# 2_DDR4_16bits.net
KiCad netlist of a schematic drawn in Altium Designer
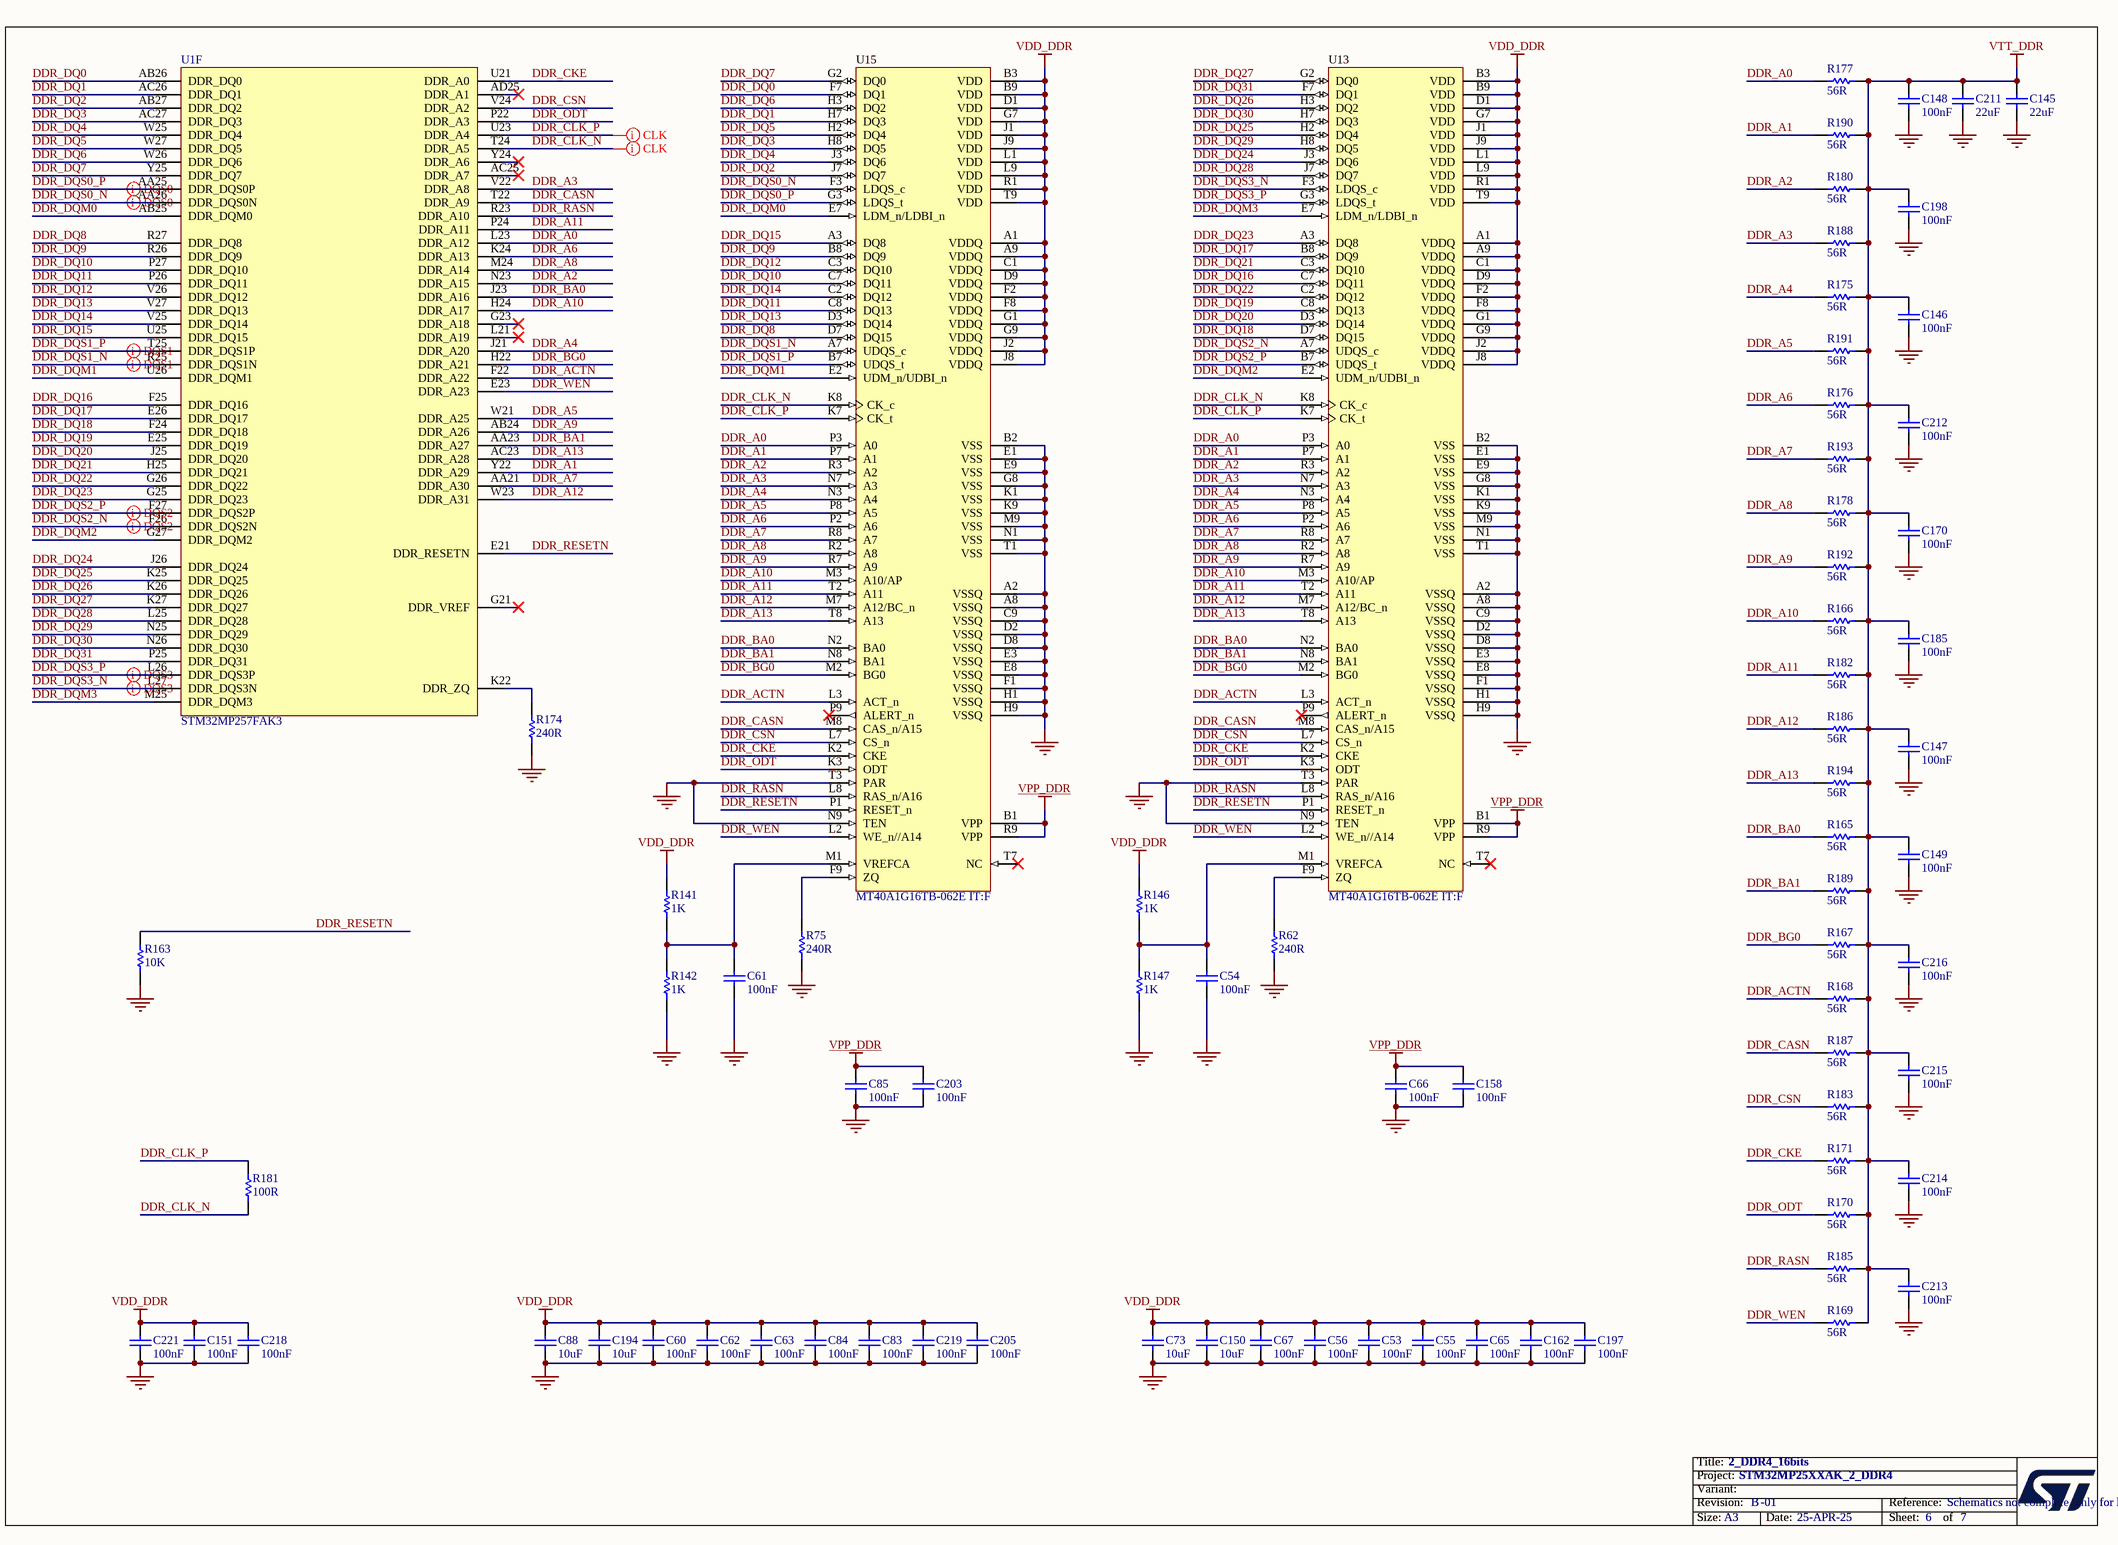
[diagram p0: 2_DDR4_16bits.SchDoc]

(export (version "E")
  (design (tool "Eeschema 10.0.6"))
  (components
    (comp (ref "C53")
      (value "100nF")
      (footprint "C0402")
      (description "Capacitor, MLCC, 100nF, 16V, X7R, +/-10%, 0402, T=0.5mm")
      (fields (field (name "INTERNAL_PART_NUMBER") "MCD-00006") (field (name "MANUFACTURER") "YAGEO"))
      (libsource (lib "MCD_PARTS_database") (part "Capacitor"))
    )
    (comp (ref "C54")
      (value "100nF")
      (footprint "C0402")
      (description "Capacitor, MLCC, 100nF, 16V, X7R, +/-10%, 0402, T=0.5mm")
      (fields (field (name "INTERNAL_PART_NUMBER") "MCD-00006") (field (name "MANUFACTURER") "YAGEO"))
      (libsource (lib "MCD_PARTS_database") (part "Capacitor"))
    )
    (comp (ref "C55")
      (value "100nF")
      (footprint "C0402")
      (description "Capacitor, MLCC, 100nF, 16V, X7R, +/-10%, 0402, T=0.5mm")
      (fields (field (name "INTERNAL_PART_NUMBER") "MCD-00006") (field (name "MANUFACTURER") "YAGEO"))
      (libsource (lib "MCD_PARTS_database") (part "Capacitor"))
    )
    (comp (ref "C56")
      (value "100nF")
      (footprint "C0402")
      (description "Capacitor, MLCC, 100nF, 16V, X7R, +/-10%, 0402, T=0.5mm")
      (fields (field (name "INTERNAL_PART_NUMBER") "MCD-00006") (field (name "MANUFACTURER") "YAGEO"))
      (libsource (lib "MCD_PARTS_database") (part "Capacitor"))
    )
    (comp (ref "C60")
      (value "100nF")
      (footprint "C0402")
      (description "Capacitor, MLCC, 100nF, 16V, X7R, +/-10%, 0402, T=0.5mm")
      (fields (field (name "INTERNAL_PART_NUMBER") "MCD-00006") (field (name "MANUFACTURER") "YAGEO"))
      (libsource (lib "MCD_PARTS_database") (part "Capacitor"))
    )
    (comp (ref "C61")
      (value "100nF")
      (footprint "C0402")
      (description "Capacitor, MLCC, 100nF, 16V, X7R, +/-10%, 0402, T=0.5mm")
      (fields (field (name "INTERNAL_PART_NUMBER") "MCD-00006") (field (name "MANUFACTURER") "YAGEO"))
      (libsource (lib "MCD_PARTS_database") (part "Capacitor"))
    )
    (comp (ref "C62")
      (value "100nF")
      (footprint "C0402")
      (description "Capacitor, MLCC, 100nF, 16V, X7R, +/-10%, 0402, T=0.5mm")
      (fields (field (name "INTERNAL_PART_NUMBER") "MCD-00006") (field (name "MANUFACTURER") "YAGEO"))
      (libsource (lib "MCD_PARTS_database") (part "Capacitor"))
    )
    (comp (ref "C63")
      (value "100nF")
      (footprint "C0402")
      (description "Capacitor, MLCC, 100nF, 16V, X7R, +/-10%, 0402, T=0.5mm")
      (fields (field (name "INTERNAL_PART_NUMBER") "MCD-00006") (field (name "MANUFACTURER") "YAGEO"))
      (libsource (lib "MCD_PARTS_database") (part "Capacitor"))
    )
    (comp (ref "C65")
      (value "100nF")
      (footprint "C0402")
      (description "Capacitor, MLCC, 100nF, 16V, X7R, +/-10%, 0402, T=0.5mm")
      (fields (field (name "INTERNAL_PART_NUMBER") "MCD-00006") (field (name "MANUFACTURER") "YAGEO"))
      (libsource (lib "MCD_PARTS_database") (part "Capacitor"))
    )
    (comp (ref "C66")
      (value "100nF")
      (footprint "C0402")
      (description "Capacitor, MLCC, 100nF, 16V, X7R, +/-10%, 0402, T=0.5mm")
      (fields (field (name "INTERNAL_PART_NUMBER") "MCD-00006") (field (name "MANUFACTURER") "YAGEO"))
      (libsource (lib "MCD_PARTS_database") (part "Capacitor"))
    )
    (comp (ref "C67")
      (value "100nF")
      (footprint "C0402")
      (description "Capacitor, MLCC, 100nF, 16V, X7R, +/-10%, 0402, T=0.5mm")
      (fields (field (name "INTERNAL_PART_NUMBER") "MCD-00006") (field (name "MANUFACTURER") "YAGEO"))
      (libsource (lib "MCD_PARTS_database") (part "Capacitor"))
    )
    (comp (ref "C73")
      (value "10uF")
      (footprint "C0603")
      (description "Capacitor, MLCC, 10uF, 6V3, X5R, +/-20%, 0603, T=0,8mm")
      (fields (field (name "INTERNAL_PART_NUMBER") "MCD-01341") (field (name "MANUFACTURER") "MURATA"))
      (libsource (lib "MCD_PARTS_database") (part "Capacitor"))
    )
    (comp (ref "C83")
      (value "100nF")
      (footprint "C0402")
      (description "Capacitor, MLCC, 100nF, 16V, X7R, +/-10%, 0402, T=0.5mm")
      (fields (field (name "INTERNAL_PART_NUMBER") "MCD-00006") (field (name "MANUFACTURER") "YAGEO"))
      (libsource (lib "MCD_PARTS_database") (part "Capacitor"))
    )
    (comp (ref "C84")
      (value "100nF")
      (footprint "C0402")
      (description "Capacitor, MLCC, 100nF, 16V, X7R, +/-10%, 0402, T=0.5mm")
      (fields (field (name "INTERNAL_PART_NUMBER") "MCD-00006") (field (name "MANUFACTURER") "YAGEO"))
      (libsource (lib "MCD_PARTS_database") (part "Capacitor"))
    )
    (comp (ref "C85")
      (value "100nF")
      (footprint "C0402")
      (description "Capacitor, MLCC, 100nF, 16V, X7R, +/-10%, 0402, T=0.5mm")
      (fields (field (name "INTERNAL_PART_NUMBER") "MCD-00006") (field (name "MANUFACTURER") "YAGEO"))
      (libsource (lib "MCD_PARTS_database") (part "Capacitor"))
    )
    (comp (ref "C88")
      (value "10uF")
      (footprint "C0603")
      (description "Capacitor, MLCC, 10uF, 6V3, X5R, +/-20%, 0603, T=0,8mm")
      (fields (field (name "INTERNAL_PART_NUMBER") "MCD-01341") (field (name "MANUFACTURER") "MURATA"))
      (libsource (lib "MCD_PARTS_database") (part "Capacitor"))
    )
    (comp (ref "C145")
      (value "22uF")
      (footprint "C0603")
      (description "Capacitor, MLCC, 22uF, 6V3, X5R, +/-20%, 0603, T=0,8mm")
      (fields (field (name "INTERNAL_PART_NUMBER") "MCD-00100") (field (name "MANUFACTURER") "MURATA"))
      (libsource (lib "MCD_PARTS_database") (part "Capacitor"))
    )
    (comp (ref "C146")
      (value "100nF")
      (footprint "C0402")
      (description "Capacitor, MLCC, 100nF, 16V, X7R, +/-10%, 0402, T=0.5mm")
      (fields (field (name "INTERNAL_PART_NUMBER") "MCD-00006") (field (name "MANUFACTURER") "YAGEO"))
      (libsource (lib "MCD_PARTS_database") (part "Capacitor"))
    )
    (comp (ref "C147")
      (value "100nF")
      (footprint "C0402")
      (description "Capacitor, MLCC, 100nF, 16V, X7R, +/-10%, 0402, T=0.5mm")
      (fields (field (name "INTERNAL_PART_NUMBER") "MCD-00006") (field (name "MANUFACTURER") "YAGEO"))
      (libsource (lib "MCD_PARTS_database") (part "Capacitor"))
    )
    (comp (ref "C148")
      (value "100nF")
      (footprint "C0402")
      (description "Capacitor, MLCC, 100nF, 16V, X7R, +/-10%, 0402, T=0.5mm")
      (fields (field (name "INTERNAL_PART_NUMBER") "MCD-00006") (field (name "MANUFACTURER") "YAGEO"))
      (libsource (lib "MCD_PARTS_database") (part "Capacitor"))
    )
    (comp (ref "C149")
      (value "100nF")
      (footprint "C0402")
      (description "Capacitor, MLCC, 100nF, 16V, X7R, +/-10%, 0402, T=0.5mm")
      (fields (field (name "INTERNAL_PART_NUMBER") "MCD-00006") (field (name "MANUFACTURER") "YAGEO"))
      (libsource (lib "MCD_PARTS_database") (part "Capacitor"))
    )
    (comp (ref "C150")
      (value "10uF")
      (footprint "C0603")
      (description "Capacitor, MLCC, 10uF, 6V3, X5R, +/-20%, 0603, T=0,8mm")
      (fields (field (name "INTERNAL_PART_NUMBER") "MCD-01341") (field (name "MANUFACTURER") "MURATA"))
      (libsource (lib "MCD_PARTS_database") (part "Capacitor"))
    )
    (comp (ref "C151")
      (value "100nF")
      (footprint "C0402")
      (description "Capacitor, MLCC, 100nF, 16V, X7R, +/-10%, 0402, T=0.5mm")
      (fields (field (name "INTERNAL_PART_NUMBER") "MCD-00006") (field (name "MANUFACTURER") "YAGEO"))
      (libsource (lib "MCD_PARTS_database") (part "Capacitor"))
    )
    (comp (ref "C158")
      (value "100nF")
      (footprint "C0402")
      (description "Capacitor, MLCC, 100nF, 16V, X7R, +/-10%, 0402, T=0.5mm")
      (fields (field (name "INTERNAL_PART_NUMBER") "MCD-00006") (field (name "MANUFACTURER") "YAGEO"))
      (libsource (lib "MCD_PARTS_database") (part "Capacitor"))
    )
    (comp (ref "C162")
      (value "100nF")
      (footprint "C0402")
      (description "Capacitor, MLCC, 100nF, 16V, X7R, +/-10%, 0402, T=0.5mm")
      (fields (field (name "INTERNAL_PART_NUMBER") "MCD-00006") (field (name "MANUFACTURER") "YAGEO"))
      (libsource (lib "MCD_PARTS_database") (part "Capacitor"))
    )
    (comp (ref "C170")
      (value "100nF")
      (footprint "C0402")
      (description "Capacitor, MLCC, 100nF, 16V, X7R, +/-10%, 0402, T=0.5mm")
      (fields (field (name "INTERNAL_PART_NUMBER") "MCD-00006") (field (name "MANUFACTURER") "YAGEO"))
      (libsource (lib "MCD_PARTS_database") (part "Capacitor"))
    )
    (comp (ref "C185")
      (value "100nF")
      (footprint "C0402")
      (description "Capacitor, MLCC, 100nF, 16V, X7R, +/-10%, 0402, T=0.5mm")
      (fields (field (name "INTERNAL_PART_NUMBER") "MCD-00006") (field (name "MANUFACTURER") "YAGEO"))
      (libsource (lib "MCD_PARTS_database") (part "Capacitor"))
    )
    (comp (ref "C194")
      (value "10uF")
      (footprint "C0603")
      (description "Capacitor, MLCC, 10uF, 6V3, X5R, +/-20%, 0603, T=0,8mm")
      (fields (field (name "INTERNAL_PART_NUMBER") "MCD-01341") (field (name "MANUFACTURER") "MURATA"))
      (libsource (lib "MCD_PARTS_database") (part "Capacitor"))
    )
    (comp (ref "C197")
      (value "100nF")
      (footprint "C0402")
      (description "Capacitor, MLCC, 100nF, 16V, X7R, +/-10%, 0402, T=0.5mm")
      (fields (field (name "INTERNAL_PART_NUMBER") "MCD-00006") (field (name "MANUFACTURER") "YAGEO"))
      (libsource (lib "MCD_PARTS_database") (part "Capacitor"))
    )
    (comp (ref "C198")
      (value "100nF")
      (footprint "C0402")
      (description "Capacitor, MLCC, 100nF, 16V, X7R, +/-10%, 0402, T=0.5mm")
      (fields (field (name "INTERNAL_PART_NUMBER") "MCD-00006") (field (name "MANUFACTURER") "YAGEO"))
      (libsource (lib "MCD_PARTS_database") (part "Capacitor"))
    )
    (comp (ref "C203")
      (value "100nF")
      (footprint "C0402")
      (description "Capacitor, MLCC, 100nF, 16V, X7R, +/-10%, 0402, T=0.5mm")
      (fields (field (name "INTERNAL_PART_NUMBER") "MCD-00006") (field (name "MANUFACTURER") "YAGEO"))
      (libsource (lib "MCD_PARTS_database") (part "Capacitor"))
    )
    (comp (ref "C205")
      (value "100nF")
      (footprint "C0402")
      (description "Capacitor, MLCC, 100nF, 16V, X7R, +/-10%, 0402, T=0.5mm")
      (fields (field (name "INTERNAL_PART_NUMBER") "MCD-00006") (field (name "MANUFACTURER") "YAGEO"))
      (libsource (lib "MCD_PARTS_database") (part "Capacitor"))
    )
    (comp (ref "C211")
      (value "22uF")
      (footprint "C0603")
      (description "Capacitor, MLCC, 22uF, 6V3, X5R, +/-20%, 0603, T=0,8mm")
      (fields (field (name "INTERNAL_PART_NUMBER") "MCD-00100") (field (name "MANUFACTURER") "MURATA"))
      (libsource (lib "MCD_PARTS_database") (part "Capacitor"))
    )
    (comp (ref "C212")
      (value "100nF")
      (footprint "C0402")
      (description "Capacitor, MLCC, 100nF, 16V, X7R, +/-10%, 0402, T=0.5mm")
      (fields (field (name "INTERNAL_PART_NUMBER") "MCD-00006") (field (name "MANUFACTURER") "YAGEO"))
      (libsource (lib "MCD_PARTS_database") (part "Capacitor"))
    )
    (comp (ref "C213")
      (value "100nF")
      (footprint "C0402")
      (description "Capacitor, MLCC, 100nF, 16V, X7R, +/-10%, 0402, T=0.5mm")
      (fields (field (name "INTERNAL_PART_NUMBER") "MCD-00006") (field (name "MANUFACTURER") "YAGEO"))
      (libsource (lib "MCD_PARTS_database") (part "Capacitor"))
    )
    (comp (ref "C214")
      (value "100nF")
      (footprint "C0402")
      (description "Capacitor, MLCC, 100nF, 16V, X7R, +/-10%, 0402, T=0.5mm")
      (fields (field (name "INTERNAL_PART_NUMBER") "MCD-00006") (field (name "MANUFACTURER") "YAGEO"))
      (libsource (lib "MCD_PARTS_database") (part "Capacitor"))
    )
    (comp (ref "C215")
      (value "100nF")
      (footprint "C0402")
      (description "Capacitor, MLCC, 100nF, 16V, X7R, +/-10%, 0402, T=0.5mm")
      (fields (field (name "INTERNAL_PART_NUMBER") "MCD-00006") (field (name "MANUFACTURER") "YAGEO"))
      (libsource (lib "MCD_PARTS_database") (part "Capacitor"))
    )
    (comp (ref "C216")
      (value "100nF")
      (footprint "C0402")
      (description "Capacitor, MLCC, 100nF, 16V, X7R, +/-10%, 0402, T=0.5mm")
      (fields (field (name "INTERNAL_PART_NUMBER") "MCD-00006") (field (name "MANUFACTURER") "YAGEO"))
      (libsource (lib "MCD_PARTS_database") (part "Capacitor"))
    )
    (comp (ref "C218")
      (value "100nF")
      (footprint "C0402")
      (description "Capacitor, MLCC, 100nF, 16V, X7R, +/-10%, 0402, T=0.5mm")
      (fields (field (name "INTERNAL_PART_NUMBER") "MCD-00006") (field (name "MANUFACTURER") "YAGEO"))
      (libsource (lib "MCD_PARTS_database") (part "Capacitor"))
    )
    (comp (ref "C219")
      (value "100nF")
      (footprint "C0402")
      (description "Capacitor, MLCC, 100nF, 16V, X7R, +/-10%, 0402, T=0.5mm")
      (fields (field (name "INTERNAL_PART_NUMBER") "MCD-00006") (field (name "MANUFACTURER") "YAGEO"))
      (libsource (lib "MCD_PARTS_database") (part "Capacitor"))
    )
    (comp (ref "C221")
      (value "100nF")
      (footprint "C0402")
      (description "Capacitor, MLCC, 100nF, 16V, X7R, +/-10%, 0402, T=0.5mm")
      (fields (field (name "INTERNAL_PART_NUMBER") "MCD-00006") (field (name "MANUFACTURER") "YAGEO"))
      (libsource (lib "MCD_PARTS_database") (part "Capacitor"))
    )
    (comp (ref "R62")
      (value "240R")
      (footprint "R0201_H0P23")
      (description "Resistor,240R,0201,1%,1/20W")
      (fields (field (name "INTERNAL_PART_NUMBER") "MCD-02253") (field (name "MANUFACTURER") "YAGEO"))
      (libsource (lib "MCD_PARTS_database") (part "Resistor"))
    )
    (comp (ref "R75")
      (value "240R")
      (footprint "R0201_H0P23")
      (description "Resistor,240R,0201,1%,1/20W")
      (fields (field (name "INTERNAL_PART_NUMBER") "MCD-02253") (field (name "MANUFACTURER") "YAGEO"))
      (libsource (lib "MCD_PARTS_database") (part "Resistor"))
    )
    (comp (ref "R141")
      (value "1K")
      (footprint "R0402")
      (description "Resistor, 1K, 0402, +/-1%,1/16W")
      (fields (field (name "INTERNAL_PART_NUMBER") "MCD-00061") (field (name "MANUFACTURER") "YAGEO"))
      (libsource (lib "MCD_PARTS_database") (part "Resistor"))
    )
    (comp (ref "R142")
      (value "1K")
      (footprint "R0402")
      (description "Resistor, 1K, 0402, +/-1%,1/16W")
      (fields (field (name "INTERNAL_PART_NUMBER") "MCD-00061") (field (name "MANUFACTURER") "YAGEO"))
      (libsource (lib "MCD_PARTS_database") (part "Resistor"))
    )
    (comp (ref "R146")
      (value "1K")
      (footprint "R0402")
      (description "Resistor, 1K, 0402, +/-1%,1/16W")
      (fields (field (name "INTERNAL_PART_NUMBER") "MCD-00061") (field (name "MANUFACTURER") "YAGEO"))
      (libsource (lib "MCD_PARTS_database") (part "Resistor"))
    )
    (comp (ref "R147")
      (value "1K")
      (footprint "R0402")
      (description "Resistor, 1K, 0402, +/-1%,1/16W")
      (fields (field (name "INTERNAL_PART_NUMBER") "MCD-00061") (field (name "MANUFACTURER") "YAGEO"))
      (libsource (lib "MCD_PARTS_database") (part "Resistor"))
    )
    (comp (ref "R163")
      (value "10K")
      (footprint "R0402")
      (description "Resistor,10K,0402,1%,1/16W")
      (fields (field (name "INTERNAL_PART_NUMBER") "MCD-00053") (field (name "BMS_PART_NUMBER") "9131590"))
      (libsource (lib "MCD_PARTS_database") (part "Resistor"))
    )
    (comp (ref "R165")
      (value "56R")
      (footprint "R0402")
      (description "Resistor, 56R, 0402, +/-1%, 1/16W")
      (fields (field (name "INTERNAL_PART_NUMBER") "MCD-00054") (field (name "MANUFACTURER") "YAGEO"))
      (libsource (lib "MCD_PARTS_database") (part "Resistor"))
    )
    (comp (ref "R166")
      (value "56R")
      (footprint "R0402")
      (description "Resistor, 56R, 0402, +/-1%, 1/16W")
      (fields (field (name "INTERNAL_PART_NUMBER") "MCD-00054") (field (name "MANUFACTURER") "YAGEO"))
      (libsource (lib "MCD_PARTS_database") (part "Resistor"))
    )
    (comp (ref "R167")
      (value "56R")
      (footprint "R0402")
      (description "Resistor, 56R, 0402, +/-1%, 1/16W")
      (fields (field (name "INTERNAL_PART_NUMBER") "MCD-00054") (field (name "MANUFACTURER") "YAGEO"))
      (libsource (lib "MCD_PARTS_database") (part "Resistor"))
    )
    (comp (ref "R168")
      (value "56R")
      (footprint "R0402")
      (description "Resistor, 56R, 0402, +/-1%, 1/16W")
      (fields (field (name "INTERNAL_PART_NUMBER") "MCD-00054") (field (name "MANUFACTURER") "YAGEO"))
      (libsource (lib "MCD_PARTS_database") (part "Resistor"))
    )
    (comp (ref "R169")
      (value "56R")
      (footprint "R0402")
      (description "Resistor, 56R, 0402, +/-1%, 1/16W")
      (fields (field (name "INTERNAL_PART_NUMBER") "MCD-00054") (field (name "MANUFACTURER") "YAGEO"))
      (libsource (lib "MCD_PARTS_database") (part "Resistor"))
    )
    (comp (ref "R170")
      (value "56R")
      (footprint "R0402")
      (description "Resistor, 56R, 0402, +/-1%, 1/16W")
      (fields (field (name "INTERNAL_PART_NUMBER") "MCD-00054") (field (name "MANUFACTURER") "YAGEO"))
      (libsource (lib "MCD_PARTS_database") (part "Resistor"))
    )
    (comp (ref "R171")
      (value "56R")
      (footprint "R0402")
      (description "Resistor, 56R, 0402, +/-1%, 1/16W")
      (fields (field (name "INTERNAL_PART_NUMBER") "MCD-00054") (field (name "MANUFACTURER") "YAGEO"))
      (libsource (lib "MCD_PARTS_database") (part "Resistor"))
    )
    (comp (ref "R174")
      (value "240R")
      (footprint "R0201_H0P23")
      (description "Resistor,240R,0201,1%,1/20W")
      (fields (field (name "INTERNAL_PART_NUMBER") "MCD-02253") (field (name "MANUFACTURER") "YAGEO"))
      (libsource (lib "MCD_PARTS_database") (part "Resistor"))
    )
    (comp (ref "R175")
      (value "56R")
      (footprint "R0402")
      (description "Resistor, 56R, 0402, +/-1%, 1/16W")
      (fields (field (name "INTERNAL_PART_NUMBER") "MCD-00054") (field (name "MANUFACTURER") "YAGEO"))
      (libsource (lib "MCD_PARTS_database") (part "Resistor"))
    )
    (comp (ref "R176")
      (value "56R")
      (footprint "R0402")
      (description "Resistor, 56R, 0402, +/-1%, 1/16W")
      (fields (field (name "INTERNAL_PART_NUMBER") "MCD-00054") (field (name "MANUFACTURER") "YAGEO"))
      (libsource (lib "MCD_PARTS_database") (part "Resistor"))
    )
    (comp (ref "R177")
      (value "56R")
      (footprint "R0402")
      (description "Resistor, 56R, 0402, +/-1%, 1/16W")
      (fields (field (name "INTERNAL_PART_NUMBER") "MCD-00054") (field (name "MANUFACTURER") "YAGEO"))
      (libsource (lib "MCD_PARTS_database") (part "Resistor"))
    )
    (comp (ref "R178")
      (value "56R")
      (footprint "R0402")
      (description "Resistor, 56R, 0402, +/-1%, 1/16W")
      (fields (field (name "INTERNAL_PART_NUMBER") "MCD-00054") (field (name "MANUFACTURER") "YAGEO"))
      (libsource (lib "MCD_PARTS_database") (part "Resistor"))
    )
    (comp (ref "R180")
      (value "56R")
      (footprint "R0402")
      (description "Resistor, 56R, 0402, +/-1%, 1/16W")
      (fields (field (name "INTERNAL_PART_NUMBER") "MCD-00054") (field (name "MANUFACTURER") "YAGEO"))
      (libsource (lib "MCD_PARTS_database") (part "Resistor"))
    )
    (comp (ref "R181")
      (value "100R")
      (footprint "R0402")
      (description "Resistor,100R,0402,0,5%,1/16W,±100ppm/°C")
      (fields (field (name "INTERNAL_PART_NUMBER") "MCD-01819") (field (name "MANUFACTURER") "YAGEO"))
      (libsource (lib "MCD_PARTS_database") (part "Resistor"))
    )
    (comp (ref "R182")
      (value "56R")
      (footprint "R0402")
      (description "Resistor, 56R, 0402, +/-1%, 1/16W")
      (fields (field (name "INTERNAL_PART_NUMBER") "MCD-00054") (field (name "MANUFACTURER") "YAGEO"))
      (libsource (lib "MCD_PARTS_database") (part "Resistor"))
    )
    (comp (ref "R183")
      (value "56R")
      (footprint "R0402")
      (description "Resistor, 56R, 0402, +/-1%, 1/16W")
      (fields (field (name "INTERNAL_PART_NUMBER") "MCD-00054") (field (name "MANUFACTURER") "YAGEO"))
      (libsource (lib "MCD_PARTS_database") (part "Resistor"))
    )
    (comp (ref "R185")
      (value "56R")
      (footprint "R0402")
      (description "Resistor, 56R, 0402, +/-1%, 1/16W")
      (fields (field (name "INTERNAL_PART_NUMBER") "MCD-00054") (field (name "MANUFACTURER") "YAGEO"))
      (libsource (lib "MCD_PARTS_database") (part "Resistor"))
    )
    (comp (ref "R186")
      (value "56R")
      (footprint "R0402")
      (description "Resistor, 56R, 0402, +/-1%, 1/16W")
      (fields (field (name "INTERNAL_PART_NUMBER") "MCD-00054") (field (name "MANUFACTURER") "YAGEO"))
      (libsource (lib "MCD_PARTS_database") (part "Resistor"))
    )
    (comp (ref "R187")
      (value "56R")
      (footprint "R0402")
      (description "Resistor, 56R, 0402, +/-1%, 1/16W")
      (fields (field (name "INTERNAL_PART_NUMBER") "MCD-00054") (field (name "MANUFACTURER") "YAGEO"))
      (libsource (lib "MCD_PARTS_database") (part "Resistor"))
    )
    (comp (ref "R188")
      (value "56R")
      (footprint "R0402")
      (description "Resistor, 56R, 0402, +/-1%, 1/16W")
      (fields (field (name "INTERNAL_PART_NUMBER") "MCD-00054") (field (name "MANUFACTURER") "YAGEO"))
      (libsource (lib "MCD_PARTS_database") (part "Resistor"))
    )
    (comp (ref "R189")
      (value "56R")
      (footprint "R0402")
      (description "Resistor, 56R, 0402, +/-1%, 1/16W")
      (fields (field (name "INTERNAL_PART_NUMBER") "MCD-00054") (field (name "MANUFACTURER") "YAGEO"))
      (libsource (lib "MCD_PARTS_database") (part "Resistor"))
    )
    (comp (ref "R190")
      (value "56R")
      (footprint "R0402")
      (description "Resistor, 56R, 0402, +/-1%, 1/16W")
      (fields (field (name "INTERNAL_PART_NUMBER") "MCD-00054") (field (name "MANUFACTURER") "YAGEO"))
      (libsource (lib "MCD_PARTS_database") (part "Resistor"))
    )
    (comp (ref "R191")
      (value "56R")
      (footprint "R0402")
      (description "Resistor, 56R, 0402, +/-1%, 1/16W")
      (fields (field (name "INTERNAL_PART_NUMBER") "MCD-00054") (field (name "MANUFACTURER") "YAGEO"))
      (libsource (lib "MCD_PARTS_database") (part "Resistor"))
    )
    (comp (ref "R192")
      (value "56R")
      (footprint "R0402")
      (description "Resistor, 56R, 0402, +/-1%, 1/16W")
      (fields (field (name "INTERNAL_PART_NUMBER") "MCD-00054") (field (name "MANUFACTURER") "YAGEO"))
      (libsource (lib "MCD_PARTS_database") (part "Resistor"))
    )
    (comp (ref "R193")
      (value "56R")
      (footprint "R0402")
      (description "Resistor, 56R, 0402, +/-1%, 1/16W")
      (fields (field (name "INTERNAL_PART_NUMBER") "MCD-00054") (field (name "MANUFACTURER") "YAGEO"))
      (libsource (lib "MCD_PARTS_database") (part "Resistor"))
    )
    (comp (ref "R194")
      (value "56R")
      (footprint "R0402")
      (description "Resistor, 56R, 0402, +/-1%, 1/16W")
      (fields (field (name "INTERNAL_PART_NUMBER") "MCD-00054") (field (name "MANUFACTURER") "YAGEO"))
      (libsource (lib "MCD_PARTS_database") (part "Resistor"))
    )
    (comp (ref "U1")
      (value "STM32MP257FAK3")
      (footprint "ICC_TFBGA424_14X14_P050_H1P20_CODE-B0A2")
      (description "MPU , 2xCortex-A35@1.5GHz, Cortex-M33@400MHz, TFBGA 14x14, pitch 0.5, 648KB SRAM, With Crypto")
      (fields
        (field (name "INTERNAL_PART_NUMBER") "MCD-03375")
        (field (name "MANUFACTURER") "STMICROELECTRONICS")
      )
      (libsource (lib "MCD_PARTS_database") (part "STM32MP257FAK3"))
    )
    (comp (ref "U13")
      (value "MT40A1G16TB-062E IT:F")
      (footprint "ICC_FBGA96_TB_7P5X13_P080")
      (description "Memory, DDR4 SDRAM, 1V2, 16Gbit, FBGA96")
      (fields (field (name "INTERNAL_PART_NUMBER") "MCD-03523") (field (name "MANUFACTURER") "MICRON"))
      (libsource (lib "MCD_PARTS_database") (part "MT40A1G16TB-062E IT{colon}F"))
    )
    (comp (ref "U15")
      (value "MT40A1G16TB-062E IT:F")
      (footprint "ICC_FBGA96_TB_7P5X13_P080")
      (description "Memory, DDR4 SDRAM, 1V2, 16Gbit, FBGA96")
      (fields (field (name "INTERNAL_PART_NUMBER") "MCD-03523") (field (name "MANUFACTURER") "MICRON"))
      (libsource (lib "MCD_PARTS_database") (part "MT40A1G16TB-062E IT{colon}F"))
    )
  )
  (nets
    (net (code "1") (name "/DDR_A0") (class "Default")
      (node (ref "R177") (pin "1") (pinfunction "1_1") (pintype "passive"))
      (node (ref "U1") (pin "L23") (pinfunction "DDR_A12_L23") (pintype "passive"))
      (node (ref "U13") (pin "P3") (pinfunction "A0_P3") (pintype "input"))
      (node (ref "U15") (pin "P3") (pinfunction "A0_P3") (pintype "input"))
    )
    (net (code "2") (name "/DDR_A1") (class "Default")
      (node (ref "R190") (pin "1") (pinfunction "1_1") (pintype "passive"))
      (node (ref "U1") (pin "Y22") (pinfunction "DDR_A29_Y22") (pintype "passive"))
      (node (ref "U13") (pin "P7") (pinfunction "A1_P7") (pintype "input"))
      (node (ref "U15") (pin "P7") (pinfunction "A1_P7") (pintype "input"))
    )
    (net (code "3") (name "/DDR_A2") (class "Default")
      (node (ref "R180") (pin "1") (pinfunction "1_1") (pintype "passive"))
      (node (ref "U1") (pin "N23") (pinfunction "DDR_A15_N23") (pintype "passive"))
      (node (ref "U13") (pin "R3") (pinfunction "A2_R3") (pintype "input"))
      (node (ref "U15") (pin "R3") (pinfunction "A2_R3") (pintype "input"))
    )
    (net (code "4") (name "/DDR_A3") (class "Default")
      (node (ref "R188") (pin "1") (pinfunction "1_1") (pintype "passive"))
      (node (ref "U1") (pin "V22") (pinfunction "DDR_A8_V22") (pintype "passive"))
      (node (ref "U13") (pin "N7") (pinfunction "A3_N7") (pintype "input"))
      (node (ref "U15") (pin "N7") (pinfunction "A3_N7") (pintype "input"))
    )
    (net (code "5") (name "/DDR_A4") (class "Default")
      (node (ref "R175") (pin "1") (pinfunction "1_1") (pintype "passive"))
      (node (ref "U1") (pin "J21") (pinfunction "DDR_A20_J21") (pintype "passive"))
      (node (ref "U13") (pin "N3") (pinfunction "A4_N3") (pintype "input"))
      (node (ref "U15") (pin "N3") (pinfunction "A4_N3") (pintype "input"))
    )
    (net (code "6") (name "/DDR_A5") (class "Default")
      (node (ref "R191") (pin "1") (pinfunction "1_1") (pintype "passive"))
      (node (ref "U1") (pin "W21") (pinfunction "DDR_A25_W21") (pintype "passive"))
      (node (ref "U13") (pin "P8") (pinfunction "A5_P8") (pintype "input"))
      (node (ref "U15") (pin "P8") (pinfunction "A5_P8") (pintype "input"))
    )
    (net (code "7") (name "/DDR_A6") (class "Default")
      (node (ref "R176") (pin "1") (pinfunction "1_1") (pintype "passive"))
      (node (ref "U1") (pin "K24") (pinfunction "DDR_A13_K24") (pintype "passive"))
      (node (ref "U13") (pin "P2") (pinfunction "A6_P2") (pintype "input"))
      (node (ref "U15") (pin "P2") (pinfunction "A6_P2") (pintype "input"))
    )
    (net (code "8") (name "/DDR_A7") (class "Default")
      (node (ref "R193") (pin "1") (pinfunction "1_1") (pintype "passive"))
      (node (ref "U1") (pin "AA21") (pinfunction "DDR_A30_AA21") (pintype "passive"))
      (node (ref "U13") (pin "R8") (pinfunction "A7_R8") (pintype "input"))
      (node (ref "U15") (pin "R8") (pinfunction "A7_R8") (pintype "input"))
    )
    (net (code "9") (name "/DDR_A8") (class "Default")
      (node (ref "R178") (pin "1") (pinfunction "1_1") (pintype "passive"))
      (node (ref "U1") (pin "M24") (pinfunction "DDR_A14_M24") (pintype "passive"))
      (node (ref "U13") (pin "R2") (pinfunction "A8_R2") (pintype "input"))
      (node (ref "U15") (pin "R2") (pinfunction "A8_R2") (pintype "input"))
    )
    (net (code "10") (name "/DDR_A9") (class "Default")
      (node (ref "R192") (pin "1") (pinfunction "1_1") (pintype "passive"))
      (node (ref "U1") (pin "AB24") (pinfunction "DDR_A26_AB24") (pintype "passive"))
      (node (ref "U13") (pin "R7") (pinfunction "A9_R7") (pintype "input"))
      (node (ref "U15") (pin "R7") (pinfunction "A9_R7") (pintype "input"))
    )
    (net (code "11") (name "/DDR_A10") (class "Default")
      (node (ref "R166") (pin "1") (pinfunction "1_1") (pintype "passive"))
      (node (ref "U1") (pin "H24") (pinfunction "DDR_A17_H24") (pintype "passive"))
      (node (ref "U13") (pin "M3") (pinfunction "A10/AP_M3") (pintype "input"))
      (node (ref "U15") (pin "M3") (pinfunction "A10/AP_M3") (pintype "input"))
    )
    (net (code "12") (name "/DDR_A11") (class "Default")
      (node (ref "R182") (pin "1") (pinfunction "1_1") (pintype "passive"))
      (node (ref "U1") (pin "P24") (pinfunction "DDR_A11_P24") (pintype "passive"))
      (node (ref "U13") (pin "T2") (pinfunction "A11_T2") (pintype "input"))
      (node (ref "U15") (pin "T2") (pinfunction "A11_T2") (pintype "input"))
    )
    (net (code "13") (name "/DDR_A12") (class "Default")
      (node (ref "R186") (pin "1") (pinfunction "1_1") (pintype "passive"))
      (node (ref "U1") (pin "W23") (pinfunction "DDR_A31_W23") (pintype "passive"))
      (node (ref "U13") (pin "M7") (pinfunction "A12/BC_n_M7") (pintype "input"))
      (node (ref "U15") (pin "M7") (pinfunction "A12/BC_n_M7") (pintype "input"))
    )
    (net (code "14") (name "/DDR_A13") (class "Default")
      (node (ref "R194") (pin "1") (pinfunction "1_1") (pintype "passive"))
      (node (ref "U1") (pin "AC23") (pinfunction "DDR_A28_AC23") (pintype "passive"))
      (node (ref "U13") (pin "T8") (pinfunction "A13_T8") (pintype "input"))
      (node (ref "U15") (pin "T8") (pinfunction "A13_T8") (pintype "input"))
    )
    (net (code "15") (name "/DDR_ACTN") (class "Default")
      (node (ref "R168") (pin "1") (pinfunction "1_1") (pintype "passive"))
      (node (ref "U1") (pin "F22") (pinfunction "DDR_A22_F22") (pintype "passive"))
      (node (ref "U13") (pin "L3") (pinfunction "ACT_n_L3") (pintype "input"))
      (node (ref "U15") (pin "L3") (pinfunction "ACT_n_L3") (pintype "input"))
    )
    (net (code "16") (name "/DDR_BA0") (class "Default")
      (node (ref "R165") (pin "1") (pinfunction "1_1") (pintype "passive"))
      (node (ref "U1") (pin "J23") (pinfunction "DDR_A16_J23") (pintype "passive"))
      (node (ref "U13") (pin "N2") (pinfunction "BA0_N2") (pintype "input"))
      (node (ref "U15") (pin "N2") (pinfunction "BA0_N2") (pintype "input"))
    )
    (net (code "17") (name "/DDR_BA1") (class "Default")
      (node (ref "R189") (pin "1") (pinfunction "1_1") (pintype "passive"))
      (node (ref "U1") (pin "AA23") (pinfunction "DDR_A27_AA23") (pintype "passive"))
      (node (ref "U13") (pin "N8") (pinfunction "BA1_N8") (pintype "input"))
      (node (ref "U15") (pin "N8") (pinfunction "BA1_N8") (pintype "input"))
    )
    (net (code "18") (name "/DDR_BG0") (class "Default")
      (node (ref "R167") (pin "1") (pinfunction "1_1") (pintype "passive"))
      (node (ref "U1") (pin "H22") (pinfunction "DDR_A21_H22") (pintype "passive"))
      (node (ref "U13") (pin "M2") (pinfunction "BG0_M2") (pintype "input"))
      (node (ref "U15") (pin "M2") (pinfunction "BG0_M2") (pintype "input"))
    )
    (net (code "19") (name "/DDR_CASN") (class "Default")
      (node (ref "R187") (pin "1") (pinfunction "1_1") (pintype "passive"))
      (node (ref "U1") (pin "T22") (pinfunction "DDR_A9_T22") (pintype "passive"))
      (node (ref "U13") (pin "M8") (pinfunction "CAS_n/A15_M8") (pintype "input"))
      (node (ref "U15") (pin "M8") (pinfunction "CAS_n/A15_M8") (pintype "input"))
    )
    (net (code "20") (name "/DDR_CKE") (class "Default")
      (node (ref "R171") (pin "1") (pinfunction "1_1") (pintype "passive"))
      (node (ref "U1") (pin "U21") (pinfunction "DDR_A0_U21") (pintype "passive"))
      (node (ref "U13") (pin "K2") (pinfunction "CKE_K2") (pintype "input"))
      (node (ref "U15") (pin "K2") (pinfunction "CKE_K2") (pintype "input"))
    )
    (net (code "21") (name "/DDR_CLK_N") (class "Default")
      (node (ref "R181") (pin "2") (pinfunction "2_2") (pintype "passive"))
      (node (ref "U1") (pin "T24") (pinfunction "DDR_A5_T24") (pintype "passive"))
      (node (ref "U13") (pin "K8") (pinfunction "CK_c_K8") (pintype "input"))
      (node (ref "U15") (pin "K8") (pinfunction "CK_c_K8") (pintype "input"))
    )
    (net (code "22") (name "/DDR_CLK_P") (class "Default")
      (node (ref "R181") (pin "1") (pinfunction "1_1") (pintype "passive"))
      (node (ref "U1") (pin "U23") (pinfunction "DDR_A4_U23") (pintype "passive"))
      (node (ref "U13") (pin "K7") (pinfunction "CK_t_K7") (pintype "input"))
      (node (ref "U15") (pin "K7") (pinfunction "CK_t_K7") (pintype "input"))
    )
    (net (code "23") (name "/DDR_CSN") (class "Default")
      (node (ref "R183") (pin "1") (pinfunction "1_1") (pintype "passive"))
      (node (ref "U1") (pin "V24") (pinfunction "DDR_A2_V24") (pintype "passive"))
      (node (ref "U13") (pin "L7") (pinfunction "CS_n_L7") (pintype "input"))
      (node (ref "U15") (pin "L7") (pinfunction "CS_n_L7") (pintype "input"))
    )
    (net (code "24") (name "/DDR_DQ0") (class "Default")
      (node (ref "U1") (pin "AB26") (pinfunction "DDR_DQ0_AB26") (pintype "passive"))
      (node (ref "U15") (pin "F7") (pinfunction "DQ1_F7") (pintype "bidirectional"))
    )
    (net (code "25") (name "/DDR_DQ1") (class "Default")
      (node (ref "U1") (pin "AC26") (pinfunction "DDR_DQ1_AC26") (pintype "passive"))
      (node (ref "U15") (pin "H7") (pinfunction "DQ3_H7") (pintype "bidirectional"))
    )
    (net (code "26") (name "/DDR_DQ2") (class "Default")
      (node (ref "U1") (pin "AB27") (pinfunction "DDR_DQ2_AB27") (pintype "passive"))
      (node (ref "U15") (pin "J7") (pinfunction "DQ7_J7") (pintype "bidirectional"))
    )
    (net (code "27") (name "/DDR_DQ3") (class "Default")
      (node (ref "U1") (pin "AC27") (pinfunction "DDR_DQ3_AC27") (pintype "passive"))
      (node (ref "U15") (pin "H8") (pinfunction "DQ5_H8") (pintype "bidirectional"))
    )
    (net (code "28") (name "/DDR_DQ4") (class "Default")
      (node (ref "U1") (pin "W25") (pinfunction "DDR_DQ4_W25") (pintype "passive"))
      (node (ref "U15") (pin "J3") (pinfunction "DQ6_J3") (pintype "bidirectional"))
    )
    (net (code "29") (name "/DDR_DQ5") (class "Default")
      (node (ref "U1") (pin "W27") (pinfunction "DDR_DQ5_W27") (pintype "passive"))
      (node (ref "U15") (pin "H2") (pinfunction "DQ4_H2") (pintype "bidirectional"))
    )
    (net (code "30") (name "/DDR_DQ6") (class "Default")
      (node (ref "U1") (pin "W26") (pinfunction "DDR_DQ6_W26") (pintype "passive"))
      (node (ref "U15") (pin "H3") (pinfunction "DQ2_H3") (pintype "bidirectional"))
    )
    (net (code "31") (name "/DDR_DQ7") (class "Default")
      (node (ref "U1") (pin "Y25") (pinfunction "DDR_DQ7_Y25") (pintype "passive"))
      (node (ref "U15") (pin "G2") (pinfunction "DQ0_G2") (pintype "bidirectional"))
    )
    (net (code "32") (name "/DDR_DQ8") (class "Default")
      (node (ref "U1") (pin "R27") (pinfunction "DDR_DQ8_R27") (pintype "passive"))
      (node (ref "U15") (pin "D7") (pinfunction "DQ15_D7") (pintype "bidirectional"))
    )
    (net (code "33") (name "/DDR_DQ9") (class "Default")
      (node (ref "U1") (pin "R26") (pinfunction "DDR_DQ9_R26") (pintype "passive"))
      (node (ref "U15") (pin "B8") (pinfunction "DQ9_B8") (pintype "bidirectional"))
    )
    (net (code "34") (name "/DDR_DQ10") (class "Default")
      (node (ref "U1") (pin "P27") (pinfunction "DDR_DQ10_P27") (pintype "passive"))
      (node (ref "U15") (pin "C7") (pinfunction "DQ11_C7") (pintype "bidirectional"))
    )
    (net (code "35") (name "/DDR_DQ11") (class "Default")
      (node (ref "U1") (pin "P26") (pinfunction "DDR_DQ11_P26") (pintype "passive"))
      (node (ref "U15") (pin "C8") (pinfunction "DQ13_C8") (pintype "bidirectional"))
    )
    (net (code "36") (name "/DDR_DQ12") (class "Default")
      (node (ref "U1") (pin "V26") (pinfunction "DDR_DQ12_V26") (pintype "passive"))
      (node (ref "U15") (pin "C3") (pinfunction "DQ10_C3") (pintype "bidirectional"))
    )
    (net (code "37") (name "/DDR_DQ13") (class "Default")
      (node (ref "U1") (pin "V27") (pinfunction "DDR_DQ13_V27") (pintype "passive"))
      (node (ref "U15") (pin "D3") (pinfunction "DQ14_D3") (pintype "bidirectional"))
    )
    (net (code "38") (name "/DDR_DQ14") (class "Default")
      (node (ref "U1") (pin "V25") (pinfunction "DDR_DQ14_V25") (pintype "passive"))
      (node (ref "U15") (pin "C2") (pinfunction "DQ12_C2") (pintype "bidirectional"))
    )
    (net (code "39") (name "/DDR_DQ15") (class "Default")
      (node (ref "U1") (pin "U25") (pinfunction "DDR_DQ15_U25") (pintype "passive"))
      (node (ref "U15") (pin "A3") (pinfunction "DQ8_A3") (pintype "bidirectional"))
    )
    (net (code "40") (name "/DDR_DQ16") (class "Default")
      (node (ref "U1") (pin "F25") (pinfunction "DDR_DQ16_F25") (pintype "passive"))
      (node (ref "U13") (pin "C7") (pinfunction "DQ11_C7") (pintype "bidirectional"))
    )
    (net (code "41") (name "/DDR_DQ17") (class "Default")
      (node (ref "U1") (pin "E26") (pinfunction "DDR_DQ17_E26") (pintype "passive"))
      (node (ref "U13") (pin "B8") (pinfunction "DQ9_B8") (pintype "bidirectional"))
    )
    (net (code "42") (name "/DDR_DQ18") (class "Default")
      (node (ref "U1") (pin "F24") (pinfunction "DDR_DQ18_F24") (pintype "passive"))
      (node (ref "U13") (pin "D7") (pinfunction "DQ15_D7") (pintype "bidirectional"))
    )
    (net (code "43") (name "/DDR_DQ19") (class "Default")
      (node (ref "U1") (pin "E25") (pinfunction "DDR_DQ19_E25") (pintype "passive"))
      (node (ref "U13") (pin "C8") (pinfunction "DQ13_C8") (pintype "bidirectional"))
    )
    (net (code "44") (name "/DDR_DQ20") (class "Default")
      (node (ref "U1") (pin "J25") (pinfunction "DDR_DQ20_J25") (pintype "passive"))
      (node (ref "U13") (pin "D3") (pinfunction "DQ14_D3") (pintype "bidirectional"))
    )
    (net (code "45") (name "/DDR_DQ21") (class "Default")
      (node (ref "U1") (pin "H25") (pinfunction "DDR_DQ21_H25") (pintype "passive"))
      (node (ref "U13") (pin "C3") (pinfunction "DQ10_C3") (pintype "bidirectional"))
    )
    (net (code "46") (name "/DDR_DQ22") (class "Default")
      (node (ref "U1") (pin "G26") (pinfunction "DDR_DQ22_G26") (pintype "passive"))
      (node (ref "U13") (pin "C2") (pinfunction "DQ12_C2") (pintype "bidirectional"))
    )
    (net (code "47") (name "/DDR_DQ23") (class "Default")
      (node (ref "U1") (pin "G25") (pinfunction "DDR_DQ23_G25") (pintype "passive"))
      (node (ref "U13") (pin "A3") (pinfunction "DQ8_A3") (pintype "bidirectional"))
    )
    (net (code "48") (name "/DDR_DQ24") (class "Default")
      (node (ref "U1") (pin "J26") (pinfunction "DDR_DQ24_J26") (pintype "passive"))
      (node (ref "U13") (pin "J3") (pinfunction "DQ6_J3") (pintype "bidirectional"))
    )
    (net (code "49") (name "/DDR_DQ25") (class "Default")
      (node (ref "U1") (pin "K25") (pinfunction "DDR_DQ25_K25") (pintype "passive"))
      (node (ref "U13") (pin "H2") (pinfunction "DQ4_H2") (pintype "bidirectional"))
    )
    (net (code "50") (name "/DDR_DQ26") (class "Default")
      (node (ref "U1") (pin "K26") (pinfunction "DDR_DQ26_K26") (pintype "passive"))
      (node (ref "U13") (pin "H3") (pinfunction "DQ2_H3") (pintype "bidirectional"))
    )
    (net (code "51") (name "/DDR_DQ27") (class "Default")
      (node (ref "U1") (pin "K27") (pinfunction "DDR_DQ27_K27") (pintype "passive"))
      (node (ref "U13") (pin "G2") (pinfunction "DQ0_G2") (pintype "bidirectional"))
    )
    (net (code "52") (name "/DDR_DQ28") (class "Default")
      (node (ref "U1") (pin "L25") (pinfunction "DDR_DQ28_L25") (pintype "passive"))
      (node (ref "U13") (pin "J7") (pinfunction "DQ7_J7") (pintype "bidirectional"))
    )
    (net (code "53") (name "/DDR_DQ29") (class "Default")
      (node (ref "U1") (pin "N25") (pinfunction "DDR_DQ29_N25") (pintype "passive"))
      (node (ref "U13") (pin "H8") (pinfunction "DQ5_H8") (pintype "bidirectional"))
    )
    (net (code "54") (name "/DDR_DQ30") (class "Default")
      (node (ref "U1") (pin "N26") (pinfunction "DDR_DQ30_N26") (pintype "passive"))
      (node (ref "U13") (pin "H7") (pinfunction "DQ3_H7") (pintype "bidirectional"))
    )
    (net (code "55") (name "/DDR_DQ31") (class "Default")
      (node (ref "U1") (pin "P25") (pinfunction "DDR_DQ31_P25") (pintype "passive"))
      (node (ref "U13") (pin "F7") (pinfunction "DQ1_F7") (pintype "bidirectional"))
    )
    (net (code "56") (name "/DDR_DQM0") (class "Default")
      (node (ref "U1") (pin "AB25") (pinfunction "DDR_DQM0_AB25") (pintype "passive"))
      (node (ref "U15") (pin "E7") (pinfunction "LDM_n/LDBI_n_E7") (pintype "input"))
    )
    (net (code "57") (name "/DDR_DQM1") (class "Default")
      (node (ref "U1") (pin "U26") (pinfunction "DDR_DQM1_U26") (pintype "passive"))
      (node (ref "U15") (pin "E2") (pinfunction "UDM_n/UDBI_n_E2") (pintype "input"))
    )
    (net (code "58") (name "/DDR_DQM2") (class "Default")
      (node (ref "U1") (pin "G27") (pinfunction "DDR_DQM2_G27") (pintype "passive"))
      (node (ref "U13") (pin "E2") (pinfunction "UDM_n/UDBI_n_E2") (pintype "input"))
    )
    (net (code "59") (name "/DDR_DQM3") (class "Default")
      (node (ref "U1") (pin "M25") (pinfunction "DDR_DQM3_M25") (pintype "passive"))
      (node (ref "U13") (pin "E7") (pinfunction "LDM_n/LDBI_n_E7") (pintype "input"))
    )
    (net (code "60") (name "/DDR_DQS0_N") (class "Default")
      (node (ref "U1") (pin "AA26") (pinfunction "DDR_DQS0N_AA26") (pintype "passive"))
      (node (ref "U15") (pin "F3") (pinfunction "LDQS_c_F3") (pintype "bidirectional"))
    )
    (net (code "61") (name "/DDR_DQS0_P") (class "Default")
      (node (ref "U1") (pin "AA25") (pinfunction "DDR_DQS0P_AA25") (pintype "passive"))
      (node (ref "U15") (pin "G3") (pinfunction "LDQS_t_G3") (pintype "bidirectional"))
    )
    (net (code "62") (name "/DDR_DQS1_N") (class "Default")
      (node (ref "U1") (pin "R25") (pinfunction "DDR_DQS1N_R25") (pintype "passive"))
      (node (ref "U15") (pin "A7") (pinfunction "UDQS_c_A7") (pintype "bidirectional"))
    )
    (net (code "63") (name "/DDR_DQS1_P") (class "Default")
      (node (ref "U1") (pin "T25") (pinfunction "DDR_DQS1P_T25") (pintype "passive"))
      (node (ref "U15") (pin "B7") (pinfunction "UDQS_t_B7") (pintype "bidirectional"))
    )
    (net (code "64") (name "/DDR_DQS2_N") (class "Default")
      (node (ref "U1") (pin "F26") (pinfunction "DDR_DQS2N_F26") (pintype "passive"))
      (node (ref "U13") (pin "A7") (pinfunction "UDQS_c_A7") (pintype "bidirectional"))
    )
    (net (code "65") (name "/DDR_DQS2_P") (class "Default")
      (node (ref "U1") (pin "F27") (pinfunction "DDR_DQS2P_F27") (pintype "passive"))
      (node (ref "U13") (pin "B7") (pinfunction "UDQS_t_B7") (pintype "bidirectional"))
    )
    (net (code "66") (name "/DDR_DQS3_N") (class "Default")
      (node (ref "U1") (pin "L27") (pinfunction "DDR_DQS3N_L27") (pintype "passive"))
      (node (ref "U13") (pin "F3") (pinfunction "LDQS_c_F3") (pintype "bidirectional"))
    )
    (net (code "67") (name "/DDR_DQS3_P") (class "Default")
      (node (ref "U1") (pin "L26") (pinfunction "DDR_DQS3P_L26") (pintype "passive"))
      (node (ref "U13") (pin "G3") (pinfunction "LDQS_t_G3") (pintype "bidirectional"))
    )
    (net (code "68") (name "/DDR_ODT") (class "Default")
      (node (ref "R170") (pin "1") (pinfunction "1_1") (pintype "passive"))
      (node (ref "U1") (pin "P22") (pinfunction "DDR_A3_P22") (pintype "passive"))
      (node (ref "U13") (pin "K3") (pinfunction "ODT_K3") (pintype "input"))
      (node (ref "U15") (pin "K3") (pinfunction "ODT_K3") (pintype "input"))
    )
    (net (code "69") (name "/DDR_RASN") (class "Default")
      (node (ref "R185") (pin "1") (pinfunction "1_1") (pintype "passive"))
      (node (ref "U1") (pin "R23") (pinfunction "DDR_A10_R23") (pintype "passive"))
      (node (ref "U13") (pin "L8") (pinfunction "RAS_n/A16_L8") (pintype "input"))
      (node (ref "U15") (pin "L8") (pinfunction "RAS_n/A16_L8") (pintype "input"))
    )
    (net (code "70") (name "/DDR_RESETN") (class "Default")
      (node (ref "R163") (pin "2") (pinfunction "2_2") (pintype "passive"))
      (node (ref "U1") (pin "E21") (pinfunction "DDR_RESETN_E21") (pintype "passive"))
      (node (ref "U13") (pin "P1") (pinfunction "RESET_n_P1") (pintype "input"))
      (node (ref "U15") (pin "P1") (pinfunction "RESET_n_P1") (pintype "input"))
    )
    (net (code "71") (name "/DDR_WEN") (class "Default")
      (node (ref "R169") (pin "1") (pinfunction "1_1") (pintype "passive"))
      (node (ref "U1") (pin "E23") (pinfunction "DDR_A23_E23") (pintype "passive"))
      (node (ref "U13") (pin "L2") (pinfunction "WE_n//A14_L2") (pintype "input"))
      (node (ref "U15") (pin "L2") (pinfunction "WE_n//A14_L2") (pintype "input"))
    )
    (net (code "72") (name "GND") (class "Default")
      (node (ref "C145") (pin "1") (pinfunction "1_1") (pintype "passive"))
      (node (ref "C146") (pin "1") (pinfunction "1_1") (pintype "passive"))
      (node (ref "C147") (pin "1") (pinfunction "1_1") (pintype "passive"))
      (node (ref "C148") (pin "1") (pinfunction "1_1") (pintype "passive"))
      (node (ref "C149") (pin "1") (pinfunction "1_1") (pintype "passive"))
      (node (ref "C150") (pin "1") (pinfunction "1_1") (pintype "passive"))
      (node (ref "C151") (pin "1") (pinfunction "1_1") (pintype "passive"))
      (node (ref "C158") (pin "1") (pinfunction "1_1") (pintype "passive"))
      (node (ref "C162") (pin "1") (pinfunction "1_1") (pintype "passive"))
      (node (ref "C170") (pin "1") (pinfunction "1_1") (pintype "passive"))
      (node (ref "C185") (pin "1") (pinfunction "1_1") (pintype "passive"))
      (node (ref "C194") (pin "1") (pinfunction "1_1") (pintype "passive"))
      (node (ref "C197") (pin "1") (pinfunction "1_1") (pintype "passive"))
      (node (ref "C198") (pin "1") (pinfunction "1_1") (pintype "passive"))
      (node (ref "C203") (pin "1") (pinfunction "1_1") (pintype "passive"))
      (node (ref "C205") (pin "1") (pinfunction "1_1") (pintype "passive"))
      (node (ref "C211") (pin "1") (pinfunction "1_1") (pintype "passive"))
      (node (ref "C212") (pin "1") (pinfunction "1_1") (pintype "passive"))
      (node (ref "C213") (pin "1") (pinfunction "1_1") (pintype "passive"))
      (node (ref "C214") (pin "1") (pinfunction "1_1") (pintype "passive"))
      (node (ref "C215") (pin "1") (pinfunction "1_1") (pintype "passive"))
      (node (ref "C216") (pin "1") (pinfunction "1_1") (pintype "passive"))
      (node (ref "C218") (pin "1") (pinfunction "1_1") (pintype "passive"))
      (node (ref "C219") (pin "1") (pinfunction "1_1") (pintype "passive"))
      (node (ref "C221") (pin "1") (pinfunction "1_1") (pintype "passive"))
      (node (ref "C53") (pin "1") (pinfunction "1_1") (pintype "passive"))
      (node (ref "C54") (pin "1") (pinfunction "1_1") (pintype "passive"))
      (node (ref "C55") (pin "1") (pinfunction "1_1") (pintype "passive"))
      (node (ref "C56") (pin "1") (pinfunction "1_1") (pintype "passive"))
      (node (ref "C60") (pin "1") (pinfunction "1_1") (pintype "passive"))
      (node (ref "C61") (pin "1") (pinfunction "1_1") (pintype "passive"))
      (node (ref "C62") (pin "1") (pinfunction "1_1") (pintype "passive"))
      (node (ref "C63") (pin "1") (pinfunction "1_1") (pintype "passive"))
      (node (ref "C65") (pin "1") (pinfunction "1_1") (pintype "passive"))
      (node (ref "C66") (pin "1") (pinfunction "1_1") (pintype "passive"))
      (node (ref "C67") (pin "1") (pinfunction "1_1") (pintype "passive"))
      (node (ref "C73") (pin "1") (pinfunction "1_1") (pintype "passive"))
      (node (ref "C83") (pin "1") (pinfunction "1_1") (pintype "passive"))
      (node (ref "C84") (pin "1") (pinfunction "1_1") (pintype "passive"))
      (node (ref "C85") (pin "1") (pinfunction "1_1") (pintype "passive"))
      (node (ref "C88") (pin "1") (pinfunction "1_1") (pintype "passive"))
      (node (ref "R142") (pin "1") (pinfunction "1_1") (pintype "passive"))
      (node (ref "R147") (pin "1") (pinfunction "1_1") (pintype "passive"))
      (node (ref "R163") (pin "1") (pinfunction "1_1") (pintype "passive"))
      (node (ref "R174") (pin "1") (pinfunction "1_1") (pintype "passive"))
      (node (ref "R62") (pin "1") (pinfunction "1_1") (pintype "passive"))
      (node (ref "R75") (pin "1") (pinfunction "1_1") (pintype "passive"))
      (node (ref "U13") (pin "A2") (pinfunction "VSSQ_A2") (pintype "power_in"))
      (node (ref "U13") (pin "A8") (pinfunction "VSSQ_A8") (pintype "power_in"))
      (node (ref "U13") (pin "B2") (pinfunction "VSS_B2") (pintype "power_in"))
      (node (ref "U13") (pin "C9") (pinfunction "VSSQ_C9") (pintype "power_in"))
      (node (ref "U13") (pin "D2") (pinfunction "VSSQ_D2") (pintype "power_in"))
      (node (ref "U13") (pin "D8") (pinfunction "VSSQ_D8") (pintype "power_in"))
      (node (ref "U13") (pin "E1") (pinfunction "VSS_E1") (pintype "power_in"))
      (node (ref "U13") (pin "E3") (pinfunction "VSSQ_E3") (pintype "power_in"))
      (node (ref "U13") (pin "E8") (pinfunction "VSSQ_E8") (pintype "power_in"))
      (node (ref "U13") (pin "E9") (pinfunction "VSS_E9") (pintype "power_in"))
      (node (ref "U13") (pin "F1") (pinfunction "VSSQ_F1") (pintype "power_in"))
      (node (ref "U13") (pin "G8") (pinfunction "VSS_G8") (pintype "power_in"))
      (node (ref "U13") (pin "H1") (pinfunction "VSSQ_H1") (pintype "power_in"))
      (node (ref "U13") (pin "H9") (pinfunction "VSSQ_H9") (pintype "power_in"))
      (node (ref "U13") (pin "K1") (pinfunction "VSS_K1") (pintype "power_in"))
      (node (ref "U13") (pin "K9") (pinfunction "VSS_K9") (pintype "power_in"))
      (node (ref "U13") (pin "M9") (pinfunction "VSS_M9") (pintype "power_in"))
      (node (ref "U13") (pin "N1") (pinfunction "VSS_N1") (pintype "power_in"))
      (node (ref "U13") (pin "N9") (pinfunction "TEN_N9") (pintype "input"))
      (node (ref "U13") (pin "T1") (pinfunction "VSS_T1") (pintype "power_in"))
      (node (ref "U13") (pin "T3") (pinfunction "PAR_T3") (pintype "input"))
      (node (ref "U15") (pin "A2") (pinfunction "VSSQ_A2") (pintype "power_in"))
      (node (ref "U15") (pin "A8") (pinfunction "VSSQ_A8") (pintype "power_in"))
      (node (ref "U15") (pin "B2") (pinfunction "VSS_B2") (pintype "power_in"))
      (node (ref "U15") (pin "C9") (pinfunction "VSSQ_C9") (pintype "power_in"))
      (node (ref "U15") (pin "D2") (pinfunction "VSSQ_D2") (pintype "power_in"))
      (node (ref "U15") (pin "D8") (pinfunction "VSSQ_D8") (pintype "power_in"))
      (node (ref "U15") (pin "E1") (pinfunction "VSS_E1") (pintype "power_in"))
      (node (ref "U15") (pin "E3") (pinfunction "VSSQ_E3") (pintype "power_in"))
      (node (ref "U15") (pin "E8") (pinfunction "VSSQ_E8") (pintype "power_in"))
      (node (ref "U15") (pin "E9") (pinfunction "VSS_E9") (pintype "power_in"))
      (node (ref "U15") (pin "F1") (pinfunction "VSSQ_F1") (pintype "power_in"))
      (node (ref "U15") (pin "G8") (pinfunction "VSS_G8") (pintype "power_in"))
      (node (ref "U15") (pin "H1") (pinfunction "VSSQ_H1") (pintype "power_in"))
      (node (ref "U15") (pin "H9") (pinfunction "VSSQ_H9") (pintype "power_in"))
      (node (ref "U15") (pin "K1") (pinfunction "VSS_K1") (pintype "power_in"))
      (node (ref "U15") (pin "K9") (pinfunction "VSS_K9") (pintype "power_in"))
      (node (ref "U15") (pin "M9") (pinfunction "VSS_M9") (pintype "power_in"))
      (node (ref "U15") (pin "N1") (pinfunction "VSS_N1") (pintype "power_in"))
      (node (ref "U15") (pin "N9") (pinfunction "TEN_N9") (pintype "input"))
      (node (ref "U15") (pin "T1") (pinfunction "VSS_T1") (pintype "power_in"))
      (node (ref "U15") (pin "T3") (pinfunction "PAR_T3") (pintype "input"))
    )
    (net (code "73") (name "Net-(U1F-DDR_ZQ)") (class "Default")
      (node (ref "R174") (pin "2") (pinfunction "2_2") (pintype "passive"))
      (node (ref "U1") (pin "K22") (pinfunction "DDR_ZQ_K22") (pintype "passive"))
    )
    (net (code "74") (name "Net-(U13-VREFCA)") (class "Default")
      (node (ref "C54") (pin "2") (pinfunction "2_2") (pintype "passive"))
      (node (ref "R146") (pin "1") (pinfunction "1_1") (pintype "passive"))
      (node (ref "R147") (pin "2") (pinfunction "2_2") (pintype "passive"))
      (node (ref "U13") (pin "M1") (pinfunction "VREFCA_M1") (pintype "input"))
    )
    (net (code "75") (name "Net-(U13-ZQ)") (class "Default")
      (node (ref "R62") (pin "2") (pinfunction "2_2") (pintype "passive"))
      (node (ref "U13") (pin "F9") (pinfunction "ZQ_F9") (pintype "input"))
    )
    (net (code "76") (name "Net-(U15-VREFCA)") (class "Default")
      (node (ref "C61") (pin "2") (pinfunction "2_2") (pintype "passive"))
      (node (ref "R141") (pin "1") (pinfunction "1_1") (pintype "passive"))
      (node (ref "R142") (pin "2") (pinfunction "2_2") (pintype "passive"))
      (node (ref "U15") (pin "M1") (pinfunction "VREFCA_M1") (pintype "input"))
    )
    (net (code "77") (name "Net-(U15-ZQ)") (class "Default")
      (node (ref "R75") (pin "2") (pinfunction "2_2") (pintype "passive"))
      (node (ref "U15") (pin "F9") (pinfunction "ZQ_F9") (pintype "input"))
    )
    (net (code "78") (name "VDD_DDR") (class "Default")
      (node (ref "C150") (pin "2") (pinfunction "2_2") (pintype "passive"))
      (node (ref "C151") (pin "2") (pinfunction "2_2") (pintype "passive"))
      (node (ref "C162") (pin "2") (pinfunction "2_2") (pintype "passive"))
      (node (ref "C194") (pin "2") (pinfunction "2_2") (pintype "passive"))
      (node (ref "C197") (pin "2") (pinfunction "2_2") (pintype "passive"))
      (node (ref "C205") (pin "2") (pinfunction "2_2") (pintype "passive"))
      (node (ref "C218") (pin "2") (pinfunction "2_2") (pintype "passive"))
      (node (ref "C219") (pin "2") (pinfunction "2_2") (pintype "passive"))
      (node (ref "C221") (pin "2") (pinfunction "2_2") (pintype "passive"))
      (node (ref "C53") (pin "2") (pinfunction "2_2") (pintype "passive"))
      (node (ref "C55") (pin "2") (pinfunction "2_2") (pintype "passive"))
      (node (ref "C56") (pin "2") (pinfunction "2_2") (pintype "passive"))
      (node (ref "C60") (pin "2") (pinfunction "2_2") (pintype "passive"))
      (node (ref "C62") (pin "2") (pinfunction "2_2") (pintype "passive"))
      (node (ref "C63") (pin "2") (pinfunction "2_2") (pintype "passive"))
      (node (ref "C65") (pin "2") (pinfunction "2_2") (pintype "passive"))
      (node (ref "C67") (pin "2") (pinfunction "2_2") (pintype "passive"))
      (node (ref "C73") (pin "2") (pinfunction "2_2") (pintype "passive"))
      (node (ref "C83") (pin "2") (pinfunction "2_2") (pintype "passive"))
      (node (ref "C84") (pin "2") (pinfunction "2_2") (pintype "passive"))
      (node (ref "C88") (pin "2") (pinfunction "2_2") (pintype "passive"))
      (node (ref "R141") (pin "2") (pinfunction "2_2") (pintype "passive"))
      (node (ref "R146") (pin "2") (pinfunction "2_2") (pintype "passive"))
      (node (ref "U13") (pin "A1") (pinfunction "VDDQ_A1") (pintype "power_in"))
      (node (ref "U13") (pin "A9") (pinfunction "VDDQ_A9") (pintype "power_in"))
      (node (ref "U13") (pin "B3") (pinfunction "VDD_B3") (pintype "power_in"))
      (node (ref "U13") (pin "B9") (pinfunction "VDD_B9") (pintype "power_in"))
      (node (ref "U13") (pin "C1") (pinfunction "VDDQ_C1") (pintype "power_in"))
      (node (ref "U13") (pin "D1") (pinfunction "VDD_D1") (pintype "power_in"))
      (node (ref "U13") (pin "D9") (pinfunction "VDDQ_D9") (pintype "power_in"))
      (node (ref "U13") (pin "F2") (pinfunction "VDDQ_F2") (pintype "power_in"))
      (node (ref "U13") (pin "F8") (pinfunction "VDDQ_F8") (pintype "power_in"))
      (node (ref "U13") (pin "G1") (pinfunction "VDDQ_G1") (pintype "power_in"))
      (node (ref "U13") (pin "G7") (pinfunction "VDD_G7") (pintype "power_in"))
      (node (ref "U13") (pin "G9") (pinfunction "VDDQ_G9") (pintype "power_in"))
      (node (ref "U13") (pin "J1") (pinfunction "VDD_J1") (pintype "power_in"))
      (node (ref "U13") (pin "J2") (pinfunction "VDDQ_J2") (pintype "power_in"))
      (node (ref "U13") (pin "J8") (pinfunction "VDDQ_J8") (pintype "power_in"))
      (node (ref "U13") (pin "J9") (pinfunction "VDD_J9") (pintype "power_in"))
      (node (ref "U13") (pin "L1") (pinfunction "VDD_L1") (pintype "power_in"))
      (node (ref "U13") (pin "L9") (pinfunction "VDD_L9") (pintype "power_in"))
      (node (ref "U13") (pin "R1") (pinfunction "VDD_R1") (pintype "power_in"))
      (node (ref "U13") (pin "T9") (pinfunction "VDD_T9") (pintype "power_in"))
      (node (ref "U15") (pin "A1") (pinfunction "VDDQ_A1") (pintype "power_in"))
      (node (ref "U15") (pin "A9") (pinfunction "VDDQ_A9") (pintype "power_in"))
      (node (ref "U15") (pin "B3") (pinfunction "VDD_B3") (pintype "power_in"))
      (node (ref "U15") (pin "B9") (pinfunction "VDD_B9") (pintype "power_in"))
      (node (ref "U15") (pin "C1") (pinfunction "VDDQ_C1") (pintype "power_in"))
      (node (ref "U15") (pin "D1") (pinfunction "VDD_D1") (pintype "power_in"))
      (node (ref "U15") (pin "D9") (pinfunction "VDDQ_D9") (pintype "power_in"))
      (node (ref "U15") (pin "F2") (pinfunction "VDDQ_F2") (pintype "power_in"))
      (node (ref "U15") (pin "F8") (pinfunction "VDDQ_F8") (pintype "power_in"))
      (node (ref "U15") (pin "G1") (pinfunction "VDDQ_G1") (pintype "power_in"))
      (node (ref "U15") (pin "G7") (pinfunction "VDD_G7") (pintype "power_in"))
      (node (ref "U15") (pin "G9") (pinfunction "VDDQ_G9") (pintype "power_in"))
      (node (ref "U15") (pin "J1") (pinfunction "VDD_J1") (pintype "power_in"))
      (node (ref "U15") (pin "J2") (pinfunction "VDDQ_J2") (pintype "power_in"))
      (node (ref "U15") (pin "J8") (pinfunction "VDDQ_J8") (pintype "power_in"))
      (node (ref "U15") (pin "J9") (pinfunction "VDD_J9") (pintype "power_in"))
      (node (ref "U15") (pin "L1") (pinfunction "VDD_L1") (pintype "power_in"))
      (node (ref "U15") (pin "L9") (pinfunction "VDD_L9") (pintype "power_in"))
      (node (ref "U15") (pin "R1") (pinfunction "VDD_R1") (pintype "power_in"))
      (node (ref "U15") (pin "T9") (pinfunction "VDD_T9") (pintype "power_in"))
    )
    (net (code "79") (name "VPP_DDR") (class "Default")
      (node (ref "C158") (pin "2") (pinfunction "2_2") (pintype "passive"))
      (node (ref "C203") (pin "2") (pinfunction "2_2") (pintype "passive"))
      (node (ref "C66") (pin "2") (pinfunction "2_2") (pintype "passive"))
      (node (ref "C85") (pin "2") (pinfunction "2_2") (pintype "passive"))
      (node (ref "U13") (pin "B1") (pinfunction "VPP_B1") (pintype "power_in"))
      (node (ref "U13") (pin "R9") (pinfunction "VPP_R9") (pintype "power_in"))
      (node (ref "U15") (pin "B1") (pinfunction "VPP_B1") (pintype "power_in"))
      (node (ref "U15") (pin "R9") (pinfunction "VPP_R9") (pintype "power_in"))
    )
    (net (code "80") (name "VTT_DDR") (class "Default")
      (node (ref "C145") (pin "2") (pinfunction "2_2") (pintype "passive"))
      (node (ref "C146") (pin "2") (pinfunction "2_2") (pintype "passive"))
      (node (ref "C147") (pin "2") (pinfunction "2_2") (pintype "passive"))
      (node (ref "C148") (pin "2") (pinfunction "2_2") (pintype "passive"))
      (node (ref "C149") (pin "2") (pinfunction "2_2") (pintype "passive"))
      (node (ref "C170") (pin "2") (pinfunction "2_2") (pintype "passive"))
      (node (ref "C185") (pin "2") (pinfunction "2_2") (pintype "passive"))
      (node (ref "C198") (pin "2") (pinfunction "2_2") (pintype "passive"))
      (node (ref "C211") (pin "2") (pinfunction "2_2") (pintype "passive"))
      (node (ref "C212") (pin "2") (pinfunction "2_2") (pintype "passive"))
      (node (ref "C213") (pin "2") (pinfunction "2_2") (pintype "passive"))
      (node (ref "C214") (pin "2") (pinfunction "2_2") (pintype "passive"))
      (node (ref "C215") (pin "2") (pinfunction "2_2") (pintype "passive"))
      (node (ref "C216") (pin "2") (pinfunction "2_2") (pintype "passive"))
      (node (ref "R165") (pin "2") (pinfunction "2_2") (pintype "passive"))
      (node (ref "R166") (pin "2") (pinfunction "2_2") (pintype "passive"))
      (node (ref "R167") (pin "2") (pinfunction "2_2") (pintype "passive"))
      (node (ref "R168") (pin "2") (pinfunction "2_2") (pintype "passive"))
      (node (ref "R169") (pin "2") (pinfunction "2_2") (pintype "passive"))
      (node (ref "R170") (pin "2") (pinfunction "2_2") (pintype "passive"))
      (node (ref "R171") (pin "2") (pinfunction "2_2") (pintype "passive"))
      (node (ref "R175") (pin "2") (pinfunction "2_2") (pintype "passive"))
      (node (ref "R176") (pin "2") (pinfunction "2_2") (pintype "passive"))
      (node (ref "R177") (pin "2") (pinfunction "2_2") (pintype "passive"))
      (node (ref "R178") (pin "2") (pinfunction "2_2") (pintype "passive"))
      (node (ref "R180") (pin "2") (pinfunction "2_2") (pintype "passive"))
      (node (ref "R182") (pin "2") (pinfunction "2_2") (pintype "passive"))
      (node (ref "R183") (pin "2") (pinfunction "2_2") (pintype "passive"))
      (node (ref "R185") (pin "2") (pinfunction "2_2") (pintype "passive"))
      (node (ref "R186") (pin "2") (pinfunction "2_2") (pintype "passive"))
      (node (ref "R187") (pin "2") (pinfunction "2_2") (pintype "passive"))
      (node (ref "R188") (pin "2") (pinfunction "2_2") (pintype "passive"))
      (node (ref "R189") (pin "2") (pinfunction "2_2") (pintype "passive"))
      (node (ref "R190") (pin "2") (pinfunction "2_2") (pintype "passive"))
      (node (ref "R191") (pin "2") (pinfunction "2_2") (pintype "passive"))
      (node (ref "R192") (pin "2") (pinfunction "2_2") (pintype "passive"))
      (node (ref "R193") (pin "2") (pinfunction "2_2") (pintype "passive"))
      (node (ref "R194") (pin "2") (pinfunction "2_2") (pintype "passive"))
    )
    (net (code "81") (name "unconnected-(U1F-DDR_A1-PadAD25)") (class "Default")
      (node (ref "U1") (pin "AD25") (pinfunction "DDR_A1_AD25") (pintype "passive+no_connect"))
    )
    (net (code "82") (name "unconnected-(U1F-DDR_A6-PadY24)") (class "Default")
      (node (ref "U1") (pin "Y24") (pinfunction "DDR_A6_Y24") (pintype "passive+no_connect"))
    )
    (net (code "83") (name "unconnected-(U1F-DDR_A7-PadAC25)") (class "Default")
      (node (ref "U1") (pin "AC25") (pinfunction "DDR_A7_AC25") (pintype "passive+no_connect"))
    )
    (net (code "84") (name "unconnected-(U1F-DDR_A18-PadG23)") (class "Default")
      (node (ref "U1") (pin "G23") (pinfunction "DDR_A18_G23") (pintype "passive+no_connect"))
    )
    (net (code "85") (name "unconnected-(U1F-DDR_A19-PadL21)") (class "Default")
      (node (ref "U1") (pin "L21") (pinfunction "DDR_A19_L21") (pintype "passive+no_connect"))
    )
    (net (code "86") (name "unconnected-(U1F-DDR_VREF-PadG21)") (class "Default")
      (node (ref "U1") (pin "G21") (pinfunction "DDR_VREF_G21") (pintype "passive+no_connect"))
    )
    (net (code "87") (name "unconnected-(U13-ALERT_n-PadP9)") (class "Default")
      (node (ref "U13") (pin "P9") (pinfunction "ALERT_n_P9") (pintype "output+no_connect"))
    )
    (net (code "88") (name "unconnected-(U13-NC-PadT7)") (class "Default")
      (node (ref "U13") (pin "T7") (pinfunction "NC_T7") (pintype "input+no_connect"))
    )
    (net (code "89") (name "unconnected-(U15-ALERT_n-PadP9)") (class "Default")
      (node (ref "U15") (pin "P9") (pinfunction "ALERT_n_P9") (pintype "output+no_connect"))
    )
    (net (code "90") (name "unconnected-(U15-NC-PadT7)") (class "Default")
      (node (ref "U15") (pin "T7") (pinfunction "NC_T7") (pintype "input+no_connect"))
    )
  )
)
